# Arduino-mini-328-Sch.net
KiCad netlist of a schematic drawn in EAGLE
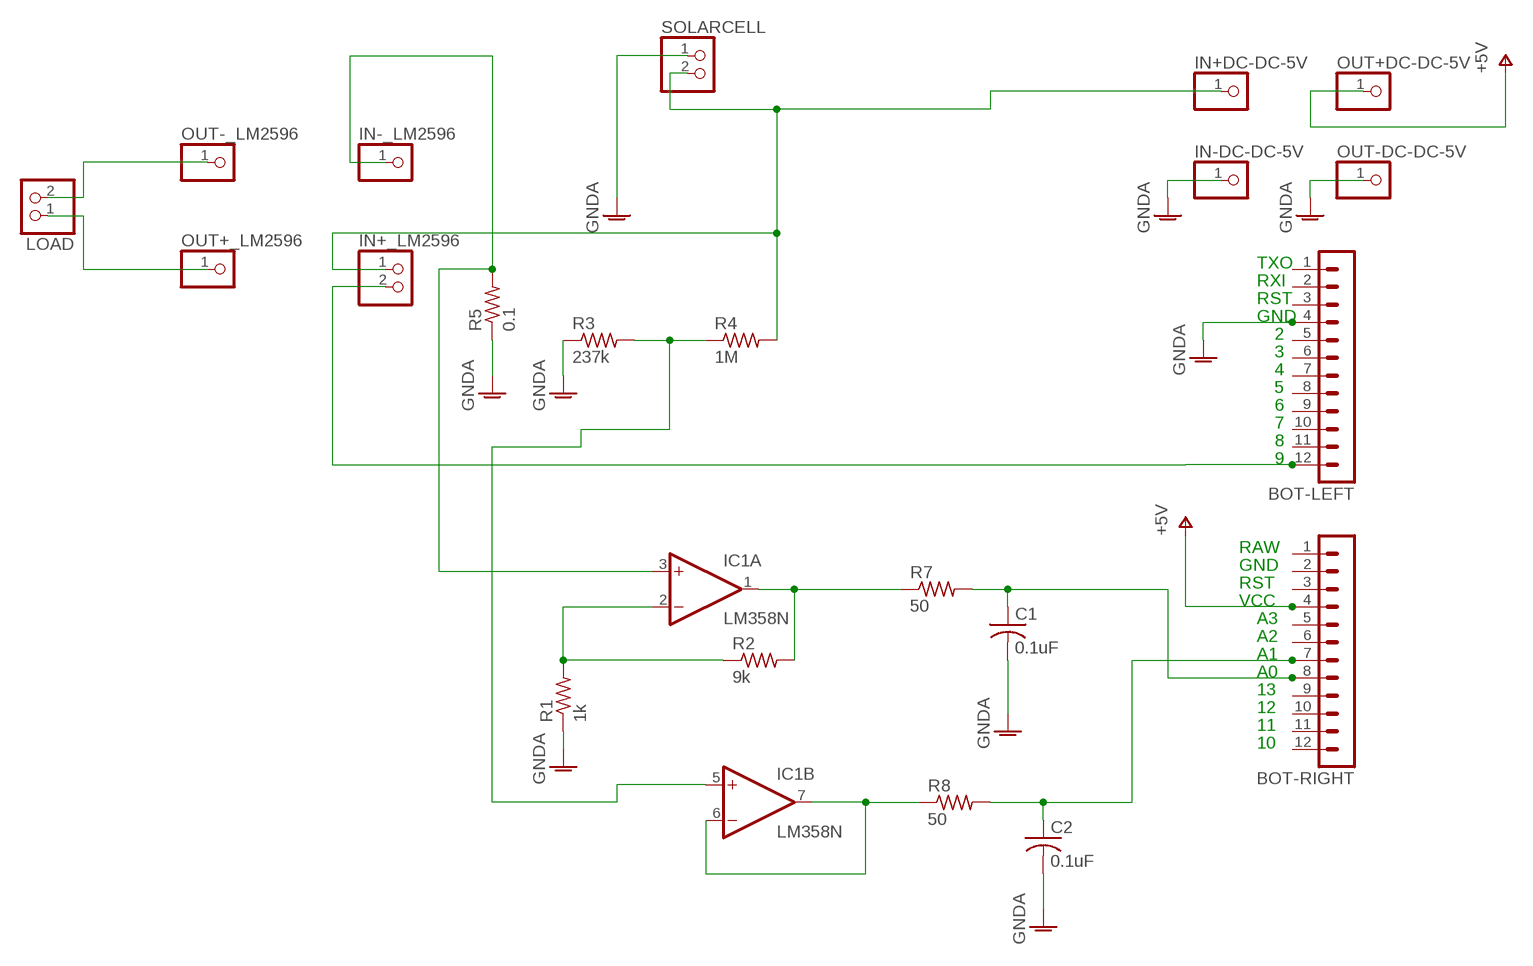
[diagram p0: schematic, sheet 1]

(export (version "E")
  (design (tool "Eeschema 10.0.6"))
  (components
    (comp (ref "BOT-LEFT")
      (value "MA12-1")
      (footprint "eagle-import:MA12-1")
      (libsource (lib "eagle-import") (part "MA12-1"))
    )
    (comp (ref "BOT-RIGHT")
      (value "MA12-1")
      (footprint "eagle-import:MA12-1")
      (libsource (lib "eagle-import") (part "MA12-1"))
    )
    (comp (ref "C1")
      (value "0.1uF")
      (footprint "eagle-import:C025-030X050")
      (libsource (lib "eagle-import") (part "C-US025-030X050"))
    )
    (comp (ref "C2")
      (value "0.1uF")
      (footprint "eagle-import:C025-030X050")
      (libsource (lib "eagle-import") (part "C-US025-030X050"))
    )
    (comp (ref "IC1")
      (value "LM358N")
      (footprint "eagle-import:DIL08")
      (libsource (lib "eagle-import") (part "LM358N"))
    )
    (comp (ref "IN+DC-DC-5V")
      (value "PINHD-1X1")
      (footprint "eagle-import:1X01")
      (libsource (lib "eagle-import") (part "PINHD-1X1"))
    )
    (comp (ref "IN+_LM2596")
      (value "PINHD-1X2/90")
      (footprint "eagle-import:1X02_90")
      (libsource (lib "eagle-import") (part "PINHD-1X2/90"))
    )
    (comp (ref "IN-DC-DC-5V")
      (value "PINHD-1X1")
      (footprint "eagle-import:1X01")
      (libsource (lib "eagle-import") (part "PINHD-1X1"))
    )
    (comp (ref "IN-_LM2596")
      (value "PINHD-1X1")
      (footprint "eagle-import:1X01")
      (libsource (lib "eagle-import") (part "PINHD-1X1"))
    )
    (comp (ref "LOAD")
      (value "PINHD-1X2")
      (footprint "eagle-import:1X02")
      (libsource (lib "eagle-import") (part "PINHD-1X2"))
    )
    (comp (ref "OUT+DC-DC-5V")
      (value "PINHD-1X1")
      (footprint "eagle-import:1X01")
      (libsource (lib "eagle-import") (part "PINHD-1X1"))
    )
    (comp (ref "OUT+_LM2596")
      (value "PINHD-1X1")
      (footprint "eagle-import:1X01")
      (libsource (lib "eagle-import") (part "PINHD-1X1"))
    )
    (comp (ref "OUT-DC-DC-5V")
      (value "PINHD-1X1")
      (footprint "eagle-import:1X01")
      (libsource (lib "eagle-import") (part "PINHD-1X1"))
    )
    (comp (ref "OUT-_LM2596")
      (value "PINHD-1X1")
      (footprint "eagle-import:1X01")
      (libsource (lib "eagle-import") (part "PINHD-1X1"))
    )
    (comp (ref "R1")
      (value "1k")
      (footprint "eagle-import:0207_10")
      (libsource (lib "eagle-import") (part "R-US_0207/10"))
    )
    (comp (ref "R2")
      (value "9k")
      (footprint "eagle-import:0207_10")
      (libsource (lib "eagle-import") (part "R-US_0207/10"))
    )
    (comp (ref "R3")
      (value "237k")
      (footprint "eagle-import:0207_10")
      (libsource (lib "eagle-import") (part "R-US_0207/10"))
    )
    (comp (ref "R4")
      (value "1M")
      (footprint "eagle-import:0207_10")
      (libsource (lib "eagle-import") (part "R-US_0207/10"))
    )
    (comp (ref "R5")
      (value "0.1")
      (footprint "eagle-import:0207_10")
      (libsource (lib "eagle-import") (part "R-US_0207/10"))
    )
    (comp (ref "R7")
      (value "50")
      (footprint "eagle-import:0207_10")
      (libsource (lib "eagle-import") (part "R-US_0207/10"))
    )
    (comp (ref "R8")
      (value "50")
      (footprint "eagle-import:0207_10")
      (libsource (lib "eagle-import") (part "R-US_0207/10"))
    )
    (comp (ref "SOLARCELL")
      (value "PINHD-1X2")
      (footprint "eagle-import:1X02")
      (libsource (lib "eagle-import") (part "PINHD-1X2"))
    )
  )
  (nets
    (net (code "1") (name "+5V") (class "Default")
      (node (ref "BOT-RIGHT") (pin "4") (pinfunction "4_4") (pintype "passive"))
      (node (ref "OUT+DC-DC-5V") (pin "1") (pinfunction "1_1") (pintype "passive"))
    )
    (net (code "2") (name "GNDA") (class "Default")
      (node (ref "BOT-LEFT") (pin "4") (pinfunction "4_4") (pintype "passive"))
      (node (ref "C1") (pin "2") (pinfunction "2_2") (pintype "passive"))
      (node (ref "C2") (pin "2") (pinfunction "2_2") (pintype "passive"))
      (node (ref "IN-DC-DC-5V") (pin "1") (pinfunction "1_1") (pintype "passive"))
      (node (ref "OUT-DC-DC-5V") (pin "1") (pinfunction "1_1") (pintype "passive"))
      (node (ref "R1") (pin "1") (pinfunction "1_1") (pintype "passive"))
      (node (ref "R3") (pin "1") (pinfunction "1_1") (pintype "passive"))
      (node (ref "R5") (pin "1") (pinfunction "1_1") (pintype "passive"))
      (node (ref "SOLARCELL") (pin "1") (pinfunction "1_1") (pintype "passive"))
    )
    (net (code "3") (name "Net-(BOT-LEFT-Pad12)") (class "Default")
      (node (ref "BOT-LEFT") (pin "12") (pinfunction "12_12") (pintype "passive"))
      (node (ref "IN+_LM2596") (pin "2") (pinfunction "2_2") (pintype "passive"))
    )
    (net (code "4") (name "Net-(BOT-RIGHT-Pad7)") (class "Default")
      (node (ref "BOT-RIGHT") (pin "7") (pinfunction "7_7") (pintype "passive"))
      (node (ref "C2") (pin "1") (pinfunction "1_1") (pintype "passive"))
      (node (ref "R8") (pin "2") (pinfunction "2_2") (pintype "passive"))
    )
    (net (code "5") (name "Net-(BOT-RIGHT-Pad8)") (class "Default")
      (node (ref "BOT-RIGHT") (pin "8") (pinfunction "8_8") (pintype "passive"))
      (node (ref "C1") (pin "1") (pinfunction "1_1") (pintype "passive"))
      (node (ref "R7") (pin "2") (pinfunction "2_2") (pintype "passive"))
    )
    (net (code "6") (name "Net-(IC1A-+IN)") (class "Default")
      (node (ref "IC1") (pin "3") (pinfunction "+IN_3") (pintype "input"))
      (node (ref "IN-_LM2596") (pin "1") (pinfunction "1_1") (pintype "passive"))
      (node (ref "R5") (pin "2") (pinfunction "2_2") (pintype "passive"))
    )
    (net (code "7") (name "Net-(IC1A--IN)") (class "Default")
      (node (ref "IC1") (pin "2") (pinfunction "-IN_2") (pintype "input"))
      (node (ref "R1") (pin "2") (pinfunction "2_2") (pintype "passive"))
      (node (ref "R2") (pin "1") (pinfunction "1_1") (pintype "passive"))
    )
    (net (code "8") (name "Net-(IC1A-OUT)") (class "Default")
      (node (ref "IC1") (pin "1") (pinfunction "OUT_1") (pintype "output"))
      (node (ref "R2") (pin "2") (pinfunction "2_2") (pintype "passive"))
      (node (ref "R7") (pin "1") (pinfunction "1_1") (pintype "passive"))
    )
    (net (code "9") (name "Net-(IC1B-+IN)") (class "Default")
      (node (ref "IC1") (pin "5") (pinfunction "+IN_5") (pintype "input"))
      (node (ref "R3") (pin "2") (pinfunction "2_2") (pintype "passive"))
      (node (ref "R4") (pin "1") (pinfunction "1_1") (pintype "passive"))
    )
    (net (code "10") (name "Net-(IC1B--IN)") (class "Default")
      (node (ref "IC1") (pin "6") (pinfunction "-IN_6") (pintype "input"))
      (node (ref "IC1") (pin "7") (pinfunction "OUT_7") (pintype "output"))
      (node (ref "R8") (pin "1") (pinfunction "1_1") (pintype "passive"))
    )
    (net (code "11") (name "Net-(IN+DC-DC-5V-Pad1)") (class "Default")
      (node (ref "IN+DC-DC-5V") (pin "1") (pinfunction "1_1") (pintype "passive"))
      (node (ref "IN+_LM2596") (pin "1") (pinfunction "1_1") (pintype "passive"))
      (node (ref "R4") (pin "2") (pinfunction "2_2") (pintype "passive"))
      (node (ref "SOLARCELL") (pin "2") (pinfunction "2_2") (pintype "passive"))
    )
    (net (code "12") (name "Net-(LOAD-Pad1)") (class "Default")
      (node (ref "LOAD") (pin "1") (pinfunction "1_1") (pintype "passive"))
      (node (ref "OUT+_LM2596") (pin "1") (pinfunction "1_1") (pintype "passive"))
    )
    (net (code "13") (name "Net-(LOAD-Pad2)") (class "Default")
      (node (ref "LOAD") (pin "2") (pinfunction "2_2") (pintype "passive"))
      (node (ref "OUT-_LM2596") (pin "1") (pinfunction "1_1") (pintype "passive"))
    )
    (net (code "14") (name "unconnected-(BOT-LEFT-Pad1)") (class "Default")
      (node (ref "BOT-LEFT") (pin "1") (pinfunction "1_1") (pintype "passive"))
    )
    (net (code "15") (name "unconnected-(BOT-LEFT-Pad2)") (class "Default")
      (node (ref "BOT-LEFT") (pin "2") (pinfunction "2_2") (pintype "passive"))
    )
    (net (code "16") (name "unconnected-(BOT-LEFT-Pad3)") (class "Default")
      (node (ref "BOT-LEFT") (pin "3") (pinfunction "3_3") (pintype "passive"))
    )
    (net (code "17") (name "unconnected-(BOT-LEFT-Pad5)") (class "Default")
      (node (ref "BOT-LEFT") (pin "5") (pinfunction "5_5") (pintype "passive"))
    )
    (net (code "18") (name "unconnected-(BOT-LEFT-Pad6)") (class "Default")
      (node (ref "BOT-LEFT") (pin "6") (pinfunction "6_6") (pintype "passive"))
    )
    (net (code "19") (name "unconnected-(BOT-LEFT-Pad7)") (class "Default")
      (node (ref "BOT-LEFT") (pin "7") (pinfunction "7_7") (pintype "passive"))
    )
    (net (code "20") (name "unconnected-(BOT-LEFT-Pad8)") (class "Default")
      (node (ref "BOT-LEFT") (pin "8") (pinfunction "8_8") (pintype "passive"))
    )
    (net (code "21") (name "unconnected-(BOT-LEFT-Pad9)") (class "Default")
      (node (ref "BOT-LEFT") (pin "9") (pinfunction "9_9") (pintype "passive"))
    )
    (net (code "22") (name "unconnected-(BOT-LEFT-Pad10)") (class "Default")
      (node (ref "BOT-LEFT") (pin "10") (pinfunction "10_10") (pintype "passive"))
    )
    (net (code "23") (name "unconnected-(BOT-LEFT-Pad11)") (class "Default")
      (node (ref "BOT-LEFT") (pin "11") (pinfunction "11_11") (pintype "passive"))
    )
    (net (code "24") (name "unconnected-(BOT-RIGHT-Pad1)") (class "Default")
      (node (ref "BOT-RIGHT") (pin "1") (pinfunction "1_1") (pintype "passive"))
    )
    (net (code "25") (name "unconnected-(BOT-RIGHT-Pad2)") (class "Default")
      (node (ref "BOT-RIGHT") (pin "2") (pinfunction "2_2") (pintype "passive"))
    )
    (net (code "26") (name "unconnected-(BOT-RIGHT-Pad3)") (class "Default")
      (node (ref "BOT-RIGHT") (pin "3") (pinfunction "3_3") (pintype "passive"))
    )
    (net (code "27") (name "unconnected-(BOT-RIGHT-Pad5)") (class "Default")
      (node (ref "BOT-RIGHT") (pin "5") (pinfunction "5_5") (pintype "passive"))
    )
    (net (code "28") (name "unconnected-(BOT-RIGHT-Pad6)") (class "Default")
      (node (ref "BOT-RIGHT") (pin "6") (pinfunction "6_6") (pintype "passive"))
    )
    (net (code "29") (name "unconnected-(BOT-RIGHT-Pad9)") (class "Default")
      (node (ref "BOT-RIGHT") (pin "9") (pinfunction "9_9") (pintype "passive"))
    )
    (net (code "30") (name "unconnected-(BOT-RIGHT-Pad10)") (class "Default")
      (node (ref "BOT-RIGHT") (pin "10") (pinfunction "10_10") (pintype "passive"))
    )
    (net (code "31") (name "unconnected-(BOT-RIGHT-Pad11)") (class "Default")
      (node (ref "BOT-RIGHT") (pin "11") (pinfunction "11_11") (pintype "passive"))
    )
    (net (code "32") (name "unconnected-(BOT-RIGHT-Pad12)") (class "Default")
      (node (ref "BOT-RIGHT") (pin "12") (pinfunction "12_12") (pintype "passive"))
    )
  )
)
